# mixer_4x1_v1.net
KiCad netlist of a schematic drawn in EAGLE
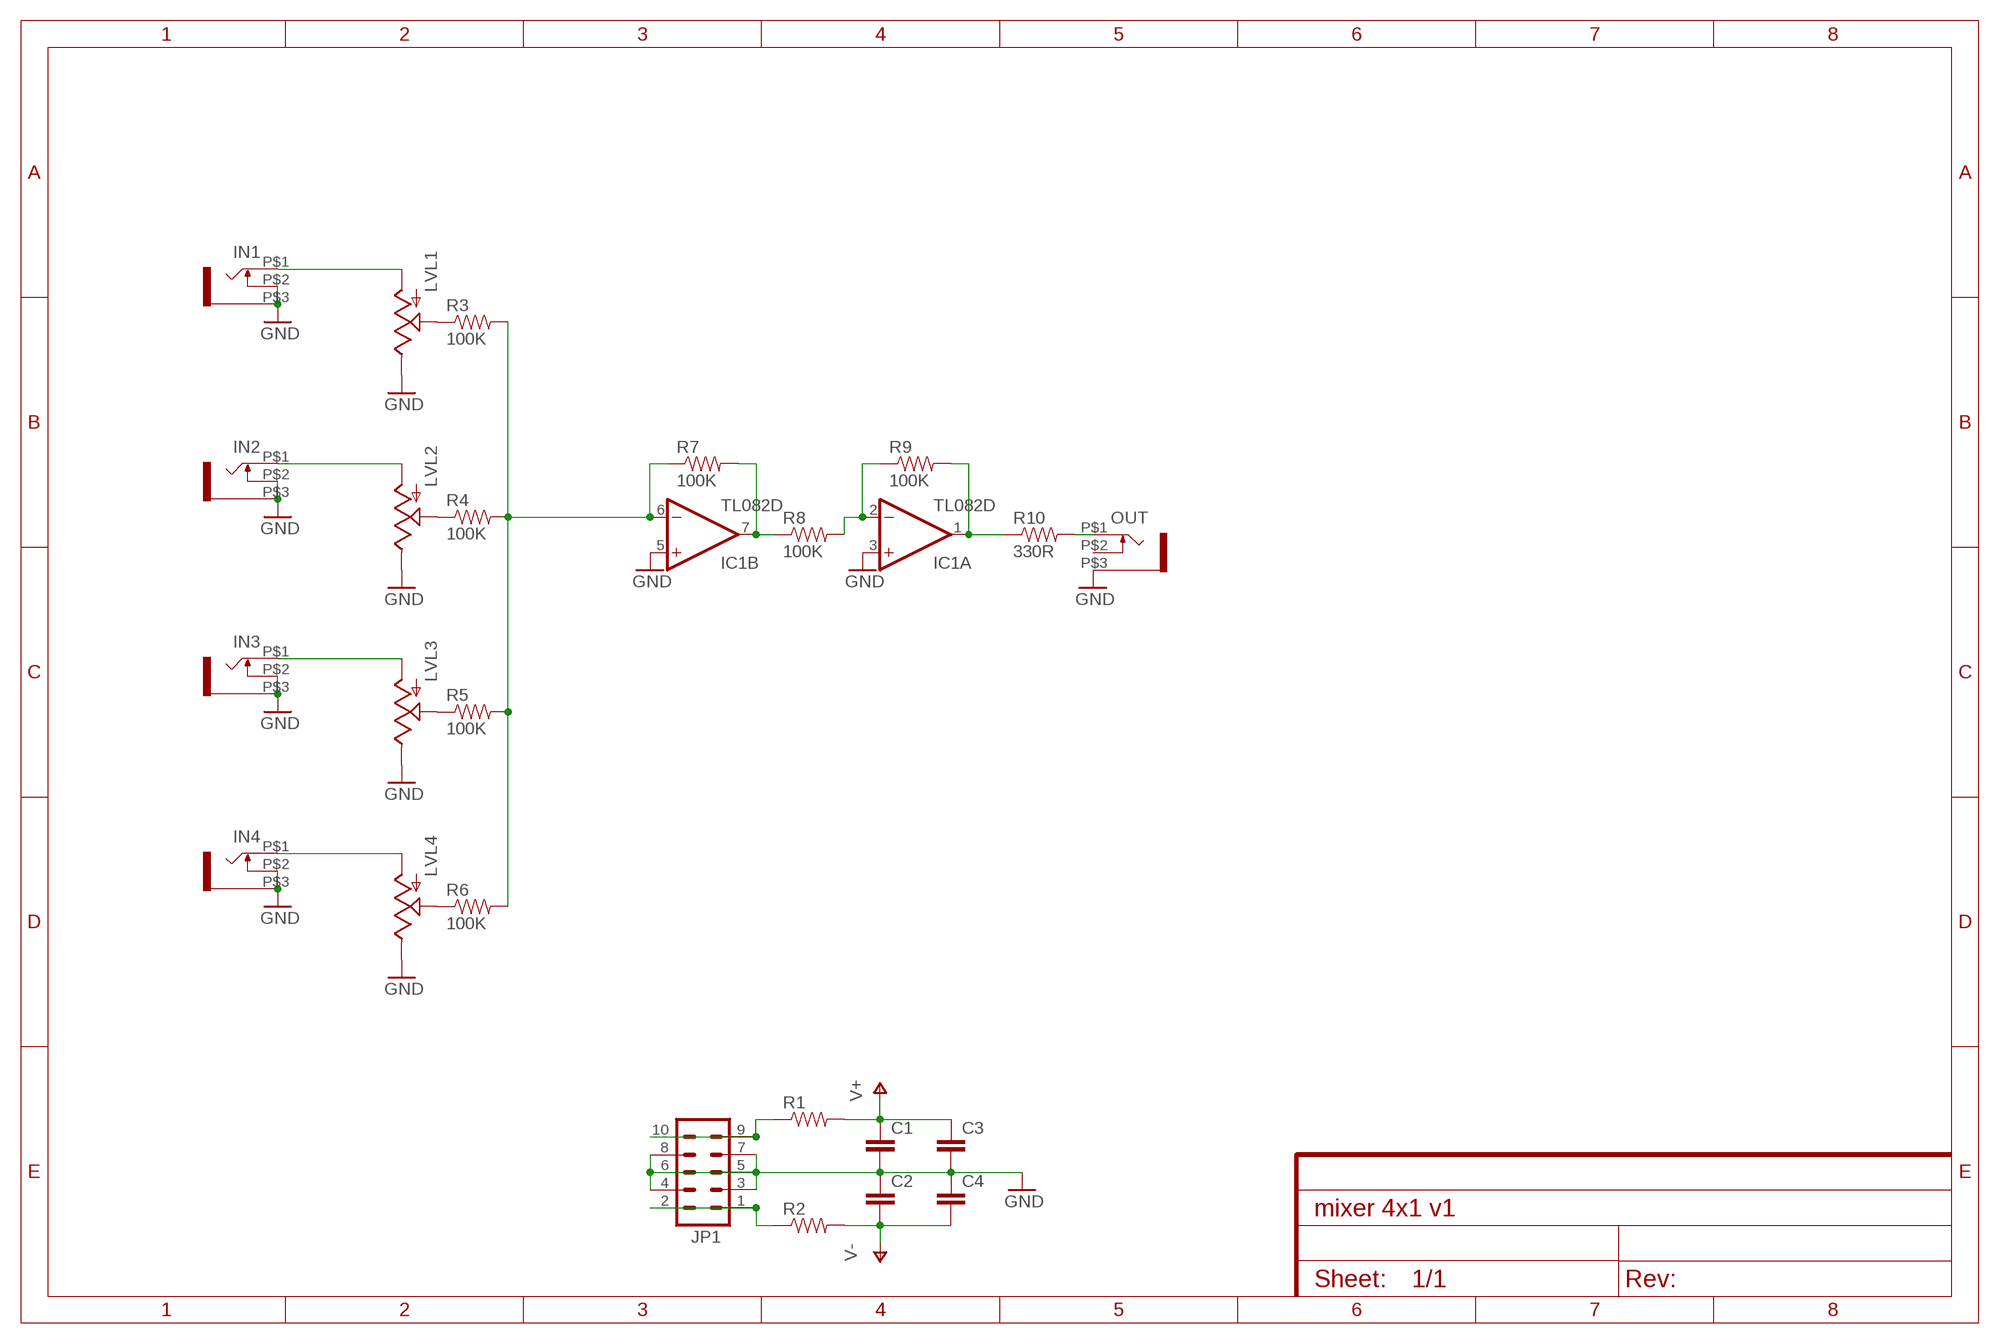
[diagram p0: schematic, sheet 1]

(export (version "E")
  (design (tool "Eeschema 10.0.6"))
  (components
    (comp (ref "C1")
      (value "CAP1206")
      (footprint "eagle-import:1206")
      (libsource (lib "eagle-import") (part "CAP1206"))
    )
    (comp (ref "C2")
      (value "CAP1206")
      (footprint "eagle-import:1206")
      (libsource (lib "eagle-import") (part "CAP1206"))
    )
    (comp (ref "C3")
      (value "CAP0805")
      (footprint "eagle-import:0805")
      (libsource (lib "eagle-import") (part "CAP0805"))
    )
    (comp (ref "C4")
      (value "CAP0805")
      (footprint "eagle-import:0805")
      (libsource (lib "eagle-import") (part "CAP0805"))
    )
    (comp (ref "IC1")
      (value "TL082D")
      (footprint "eagle-import:SO08")
      (libsource (lib "eagle-import") (part "TL082D"))
    )
    (comp (ref "IN1")
      (value "WQP-PJ301M-12_JACK")
      (footprint "eagle-import:WQP-PJ301M-12_JACK")
      (libsource (lib "eagle-import") (part "WQP-PJ301M-12_JACK"))
    )
    (comp (ref "IN2")
      (value "WQP-PJ301M-12_JACK")
      (footprint "eagle-import:WQP-PJ301M-12_JACK")
      (libsource (lib "eagle-import") (part "WQP-PJ301M-12_JACK"))
    )
    (comp (ref "IN3")
      (value "WQP-PJ301M-12_JACK")
      (footprint "eagle-import:WQP-PJ301M-12_JACK")
      (libsource (lib "eagle-import") (part "WQP-PJ301M-12_JACK"))
    )
    (comp (ref "IN4")
      (value "WQP-PJ301M-12_JACK")
      (footprint "eagle-import:WQP-PJ301M-12_JACK")
      (libsource (lib "eagle-import") (part "WQP-PJ301M-12_JACK"))
    )
    (comp (ref "JP1")
      (value "M05X2PTH")
      (footprint "eagle-import:AVR_ICSP")
      (libsource (lib "eagle-import") (part "M05X2PTH"))
    )
    (comp (ref "LVL1")
      (value "POT")
      (footprint "eagle-import:ALPS_POT")
      (libsource (lib "eagle-import") (part "POT"))
    )
    (comp (ref "LVL2")
      (value "POT")
      (footprint "eagle-import:ALPS_POT")
      (libsource (lib "eagle-import") (part "POT"))
    )
    (comp (ref "LVL3")
      (value "POT")
      (footprint "eagle-import:ALPS_POT")
      (libsource (lib "eagle-import") (part "POT"))
    )
    (comp (ref "LVL4")
      (value "POT")
      (footprint "eagle-import:ALPS_POT")
      (libsource (lib "eagle-import") (part "POT"))
    )
    (comp (ref "OUT")
      (value "WQP-PJ301M-12_JACK")
      (footprint "eagle-import:WQP-PJ301M-12_JACK")
      (libsource (lib "eagle-import") (part "WQP-PJ301M-12_JACK"))
    )
    (comp (ref "R1")
      (value "RESISTOR0805-RES")
      (footprint "eagle-import:0805")
      (libsource (lib "eagle-import") (part "SparkFun-Resistors_RESISTOR0805-RES"))
    )
    (comp (ref "R2")
      (value "RESISTOR0805-RES")
      (footprint "eagle-import:0805")
      (libsource (lib "eagle-import") (part "SparkFun-Resistors_RESISTOR0805-RES"))
    )
    (comp (ref "R3")
      (value "100K")
      (footprint "eagle-import:0805")
      (libsource (lib "eagle-import") (part "RESISTOR0805-RES"))
    )
    (comp (ref "R4")
      (value "100K")
      (footprint "eagle-import:0805")
      (libsource (lib "eagle-import") (part "RESISTOR0805-RES"))
    )
    (comp (ref "R5")
      (value "100K")
      (footprint "eagle-import:0805")
      (libsource (lib "eagle-import") (part "RESISTOR0805-RES"))
    )
    (comp (ref "R6")
      (value "100K")
      (footprint "eagle-import:0805")
      (libsource (lib "eagle-import") (part "RESISTOR0805-RES"))
    )
    (comp (ref "R7")
      (value "100K")
      (footprint "eagle-import:0805")
      (libsource (lib "eagle-import") (part "RESISTOR0805-RES"))
    )
    (comp (ref "R8")
      (value "100K")
      (footprint "eagle-import:0805")
      (libsource (lib "eagle-import") (part "RESISTOR0805-RES"))
    )
    (comp (ref "R9")
      (value "100K")
      (footprint "eagle-import:0805")
      (libsource (lib "eagle-import") (part "RESISTOR0805-RES"))
    )
    (comp (ref "R10")
      (value "330R")
      (footprint "eagle-import:0805")
      (libsource (lib "eagle-import") (part "RESISTOR0805-RES"))
    )
  )
  (nets
    (net (code "1") (name "GND") (class "Default")
      (node (ref "C1") (pin "2") (pinfunction "2_2") (pintype "passive"))
      (node (ref "C2") (pin "1") (pinfunction "1_1") (pintype "passive"))
      (node (ref "C3") (pin "2") (pinfunction "2_2") (pintype "passive"))
      (node (ref "C4") (pin "1") (pinfunction "1_1") (pintype "passive"))
      (node (ref "IC1") (pin "3") (pinfunction "+IN_3") (pintype "input"))
      (node (ref "IC1") (pin "5") (pinfunction "+IN_5") (pintype "input"))
      (node (ref "IN1") (pin "P$2") (pinfunction "3_P$2") (pintype "passive"))
      (node (ref "IN1") (pin "P$3") (pinfunction "1_P$3") (pintype "passive"))
      (node (ref "IN2") (pin "P$2") (pinfunction "3_P$2") (pintype "passive"))
      (node (ref "IN2") (pin "P$3") (pinfunction "1_P$3") (pintype "passive"))
      (node (ref "IN3") (pin "P$2") (pinfunction "3_P$2") (pintype "passive"))
      (node (ref "IN3") (pin "P$3") (pinfunction "1_P$3") (pintype "passive"))
      (node (ref "IN4") (pin "P$2") (pinfunction "3_P$2") (pintype "passive"))
      (node (ref "IN4") (pin "P$3") (pinfunction "1_P$3") (pintype "passive"))
      (node (ref "JP1") (pin "3") (pinfunction "3_3") (pintype "passive"))
      (node (ref "JP1") (pin "4") (pinfunction "4_4") (pintype "passive"))
      (node (ref "JP1") (pin "5") (pinfunction "5_5") (pintype "passive"))
      (node (ref "JP1") (pin "6") (pinfunction "6_6") (pintype "passive"))
      (node (ref "JP1") (pin "7") (pinfunction "7_7") (pintype "passive"))
      (node (ref "JP1") (pin "8") (pinfunction "8_8") (pintype "passive"))
      (node (ref "LVL1") (pin "P$1") (pinfunction "E_P$1") (pintype "passive"))
      (node (ref "LVL2") (pin "P$1") (pinfunction "E_P$1") (pintype "passive"))
      (node (ref "LVL3") (pin "P$1") (pinfunction "E_P$1") (pintype "passive"))
      (node (ref "LVL4") (pin "P$1") (pinfunction "E_P$1") (pintype "passive"))
      (node (ref "OUT") (pin "P$3") (pinfunction "1_P$3") (pintype "passive"))
    )
    (net (code "2") (name "Net-(IC1A--IN)") (class "Default")
      (node (ref "IC1") (pin "2") (pinfunction "-IN_2") (pintype "input"))
      (node (ref "R8") (pin "2") (pinfunction "2_2") (pintype "passive"))
      (node (ref "R9") (pin "1") (pinfunction "1_1") (pintype "passive"))
    )
    (net (code "3") (name "Net-(IC1A-OUT)") (class "Default")
      (node (ref "IC1") (pin "1") (pinfunction "OUT_1") (pintype "output"))
      (node (ref "R10") (pin "1") (pinfunction "1_1") (pintype "passive"))
      (node (ref "R9") (pin "2") (pinfunction "2_2") (pintype "passive"))
    )
    (net (code "4") (name "Net-(IC1B--IN)") (class "Default")
      (node (ref "IC1") (pin "6") (pinfunction "-IN_6") (pintype "input"))
      (node (ref "R3") (pin "2") (pinfunction "2_2") (pintype "passive"))
      (node (ref "R4") (pin "2") (pinfunction "2_2") (pintype "passive"))
      (node (ref "R5") (pin "2") (pinfunction "2_2") (pintype "passive"))
      (node (ref "R6") (pin "2") (pinfunction "2_2") (pintype "passive"))
      (node (ref "R7") (pin "1") (pinfunction "1_1") (pintype "passive"))
    )
    (net (code "5") (name "Net-(IC1B-OUT)") (class "Default")
      (node (ref "IC1") (pin "7") (pinfunction "OUT_7") (pintype "output"))
      (node (ref "R7") (pin "2") (pinfunction "2_2") (pintype "passive"))
      (node (ref "R8") (pin "1") (pinfunction "1_1") (pintype "passive"))
    )
    (net (code "6") (name "Net-(IN1-2)") (class "Default")
      (node (ref "IN1") (pin "P$1") (pinfunction "2_P$1") (pintype "passive"))
      (node (ref "LVL1") (pin "P$3") (pinfunction "A_P$3") (pintype "passive"))
    )
    (net (code "7") (name "Net-(IN2-2)") (class "Default")
      (node (ref "IN2") (pin "P$1") (pinfunction "2_P$1") (pintype "passive"))
      (node (ref "LVL2") (pin "P$3") (pinfunction "A_P$3") (pintype "passive"))
    )
    (net (code "8") (name "Net-(IN3-2)") (class "Default")
      (node (ref "IN3") (pin "P$1") (pinfunction "2_P$1") (pintype "passive"))
      (node (ref "LVL3") (pin "P$3") (pinfunction "A_P$3") (pintype "passive"))
    )
    (net (code "9") (name "Net-(IN4-2)") (class "Default")
      (node (ref "IN4") (pin "P$1") (pinfunction "2_P$1") (pintype "passive"))
      (node (ref "LVL4") (pin "P$3") (pinfunction "A_P$3") (pintype "passive"))
    )
    (net (code "10") (name "Net-(JP1-Pad1)") (class "Default")
      (node (ref "JP1") (pin "1") (pinfunction "1_1") (pintype "passive"))
      (node (ref "JP1") (pin "2") (pinfunction "2_2") (pintype "passive"))
      (node (ref "R2") (pin "1") (pinfunction "1_1") (pintype "passive"))
    )
    (net (code "11") (name "Net-(JP1-Pad10)") (class "Default")
      (node (ref "JP1") (pin "10") (pinfunction "10_10") (pintype "passive"))
      (node (ref "JP1") (pin "9") (pinfunction "9_9") (pintype "passive"))
      (node (ref "R1") (pin "1") (pinfunction "1_1") (pintype "passive"))
    )
    (net (code "12") (name "Net-(LVL1-S)") (class "Default")
      (node (ref "LVL1") (pin "P$2") (pinfunction "S_P$2") (pintype "passive"))
      (node (ref "R3") (pin "1") (pinfunction "1_1") (pintype "passive"))
    )
    (net (code "13") (name "Net-(LVL2-S)") (class "Default")
      (node (ref "LVL2") (pin "P$2") (pinfunction "S_P$2") (pintype "passive"))
      (node (ref "R4") (pin "1") (pinfunction "1_1") (pintype "passive"))
    )
    (net (code "14") (name "Net-(LVL3-S)") (class "Default")
      (node (ref "LVL3") (pin "P$2") (pinfunction "S_P$2") (pintype "passive"))
      (node (ref "R5") (pin "1") (pinfunction "1_1") (pintype "passive"))
    )
    (net (code "15") (name "Net-(LVL4-S)") (class "Default")
      (node (ref "LVL4") (pin "P$2") (pinfunction "S_P$2") (pintype "passive"))
      (node (ref "R6") (pin "1") (pinfunction "1_1") (pintype "passive"))
    )
    (net (code "16") (name "Net-(OUT-2)") (class "Default")
      (node (ref "OUT") (pin "P$1") (pinfunction "2_P$1") (pintype "passive"))
      (node (ref "R10") (pin "2") (pinfunction "2_2") (pintype "passive"))
    )
    (net (code "17") (name "V+") (class "Default")
      (node (ref "C1") (pin "1") (pinfunction "1_1") (pintype "passive"))
      (node (ref "C3") (pin "1") (pinfunction "1_1") (pintype "passive"))
      (node (ref "R1") (pin "2") (pinfunction "2_2") (pintype "passive"))
    )
    (net (code "18") (name "V-") (class "Default")
      (node (ref "C2") (pin "2") (pinfunction "2_2") (pintype "passive"))
      (node (ref "C4") (pin "2") (pinfunction "2_2") (pintype "passive"))
      (node (ref "R2") (pin "2") (pinfunction "2_2") (pintype "passive"))
    )
    (net (code "19") (name "unconnected-(OUT-3-PadP$2)") (class "Default")
      (node (ref "OUT") (pin "P$2") (pinfunction "3_P$2") (pintype "passive"))
    )
  )
)
